# sch.net
KiCad netlist of a schematic drawn in EAGLE
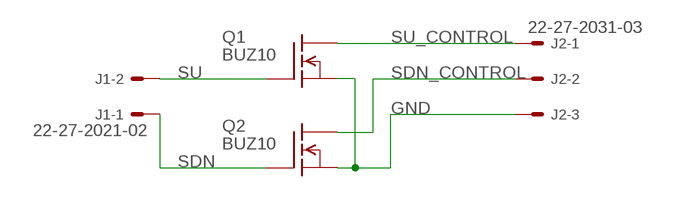
[diagram p0: schematic, sheet 1]

(export (version "E")
  (design (tool "Eeschema 10.0.6"))
  (components
    (comp (ref "J1")
      (value "22-27-2021-02")
      (footprint "eagle-import:6410-02")
      (libsource (lib "eagle-import") (part "22-?-0227-2021"))
    )
    (comp (ref "J2")
      (value "22-27-2031-03")
      (footprint "eagle-import:6410-03")
      (libsource (lib "eagle-import") (part "22-?-0327-2031"))
    )
    (comp (ref "Q1")
      (value "BUZ10")
      (footprint "eagle-import:TO220")
      (libsource (lib "eagle-import") (part "BUZ10"))
    )
    (comp (ref "Q2")
      (value "BUZ10")
      (footprint "eagle-import:TO220")
      (libsource (lib "eagle-import") (part "BUZ10"))
    )
  )
  (nets
    (net (code "1") (name "/GND") (class "Default")
      (node (ref "J2") (pin "3") (pinfunction "S_3") (pintype "passive"))
      (node (ref "Q1") (pin "3") (pinfunction "S_3") (pintype "passive"))
      (node (ref "Q2") (pin "3") (pinfunction "S_3") (pintype "passive"))
    )
    (net (code "2") (name "/SDN") (class "Default")
      (node (ref "J1") (pin "1") (pinfunction "S_1") (pintype "passive"))
      (node (ref "Q2") (pin "1") (pinfunction "G_1") (pintype "passive"))
    )
    (net (code "3") (name "/SDN_CONTROL") (class "Default")
      (node (ref "J2") (pin "2") (pinfunction "S_2") (pintype "passive"))
      (node (ref "Q2") (pin "2") (pinfunction "D_2") (pintype "passive"))
    )
    (net (code "4") (name "/SU") (class "Default")
      (node (ref "J1") (pin "2") (pinfunction "S_2") (pintype "passive"))
      (node (ref "Q1") (pin "1") (pinfunction "G_1") (pintype "passive"))
    )
    (net (code "5") (name "/SU_CONTROL") (class "Default")
      (node (ref "J2") (pin "1") (pinfunction "S_1") (pintype "passive"))
      (node (ref "Q1") (pin "2") (pinfunction "D_2") (pintype "passive"))
    )
  )
)
